# 0127-sd-card-micro.net
KiCad netlist of a schematic drawn in EAGLE
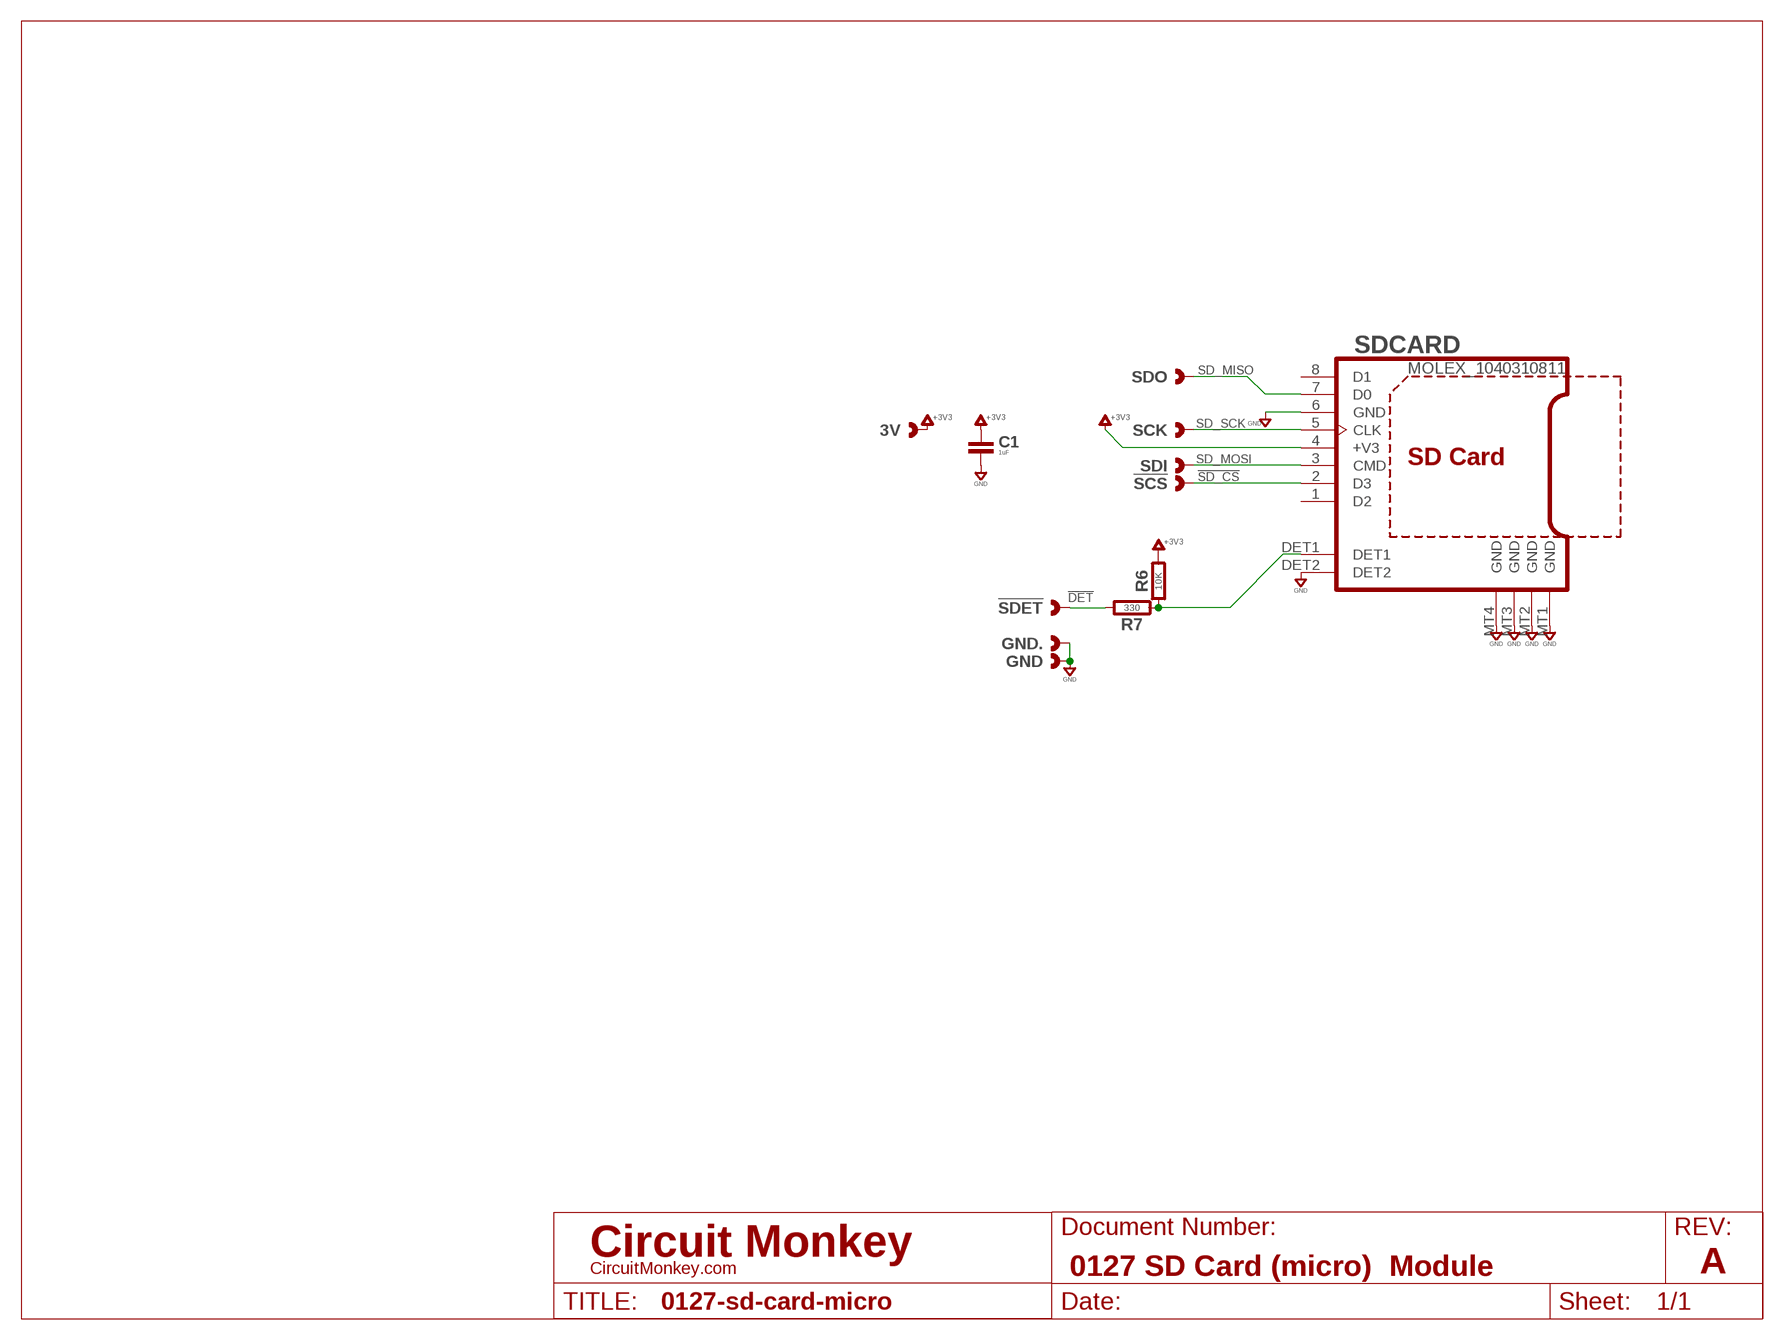
[diagram p0: schematic, sheet 1]

(export (version "E")
  (design (tool "Eeschema 10.0.6"))
  (components
    (comp (ref "!SCS")
      (value "CAST-01X12.00MM")
      (footprint "eagle-import:CAST01-2.00MM")
      (libsource (lib "eagle-import") (part "CAST-01X12.00MM"))
    )
    (comp (ref "!SDET")
      (value "CAST-01X12.00MM")
      (footprint "eagle-import:CAST01-2.00MM")
      (libsource (lib "eagle-import") (part "CAST-01X12.00MM"))
    )
    (comp (ref "3V")
      (value "CAST-01X12.00MM")
      (footprint "eagle-import:CAST01-2.00MM")
      (libsource (lib "eagle-import") (part "CAST-01X12.00MM"))
    )
    (comp (ref "C1")
      (value "1uF")
      (footprint "eagle-import:0603-CAP")
      (libsource (lib "eagle-import") (part "CAPACITOR0603"))
    )
    (comp (ref "GND")
      (value "CAST-01X12.00MM")
      (footprint "eagle-import:CAST01-2.00MM")
      (libsource (lib "eagle-import") (part "CAST-01X12.00MM"))
    )
    (comp (ref "GND.")
      (value "CAST-01X12.00MM")
      (footprint "eagle-import:CAST01-2.00MM")
      (libsource (lib "eagle-import") (part "CAST-01X12.00MM"))
    )
    (comp (ref "R6")
      (value "10K")
      (footprint "eagle-import:0603-RES")
      (libsource (lib "eagle-import") (part "RESISTOR0603"))
    )
    (comp (ref "R7")
      (value "330")
      (footprint "eagle-import:0603-RES")
      (libsource (lib "eagle-import") (part "RESISTOR0603"))
    )
    (comp (ref "SCK")
      (value "CAST-01X12.00MM")
      (footprint "eagle-import:CAST01-2.00MM")
      (libsource (lib "eagle-import") (part "CAST-01X12.00MM"))
    )
    (comp (ref "SDCARD")
      (value "MOLEX_1040310811")
      (footprint "eagle-import:MOLEX_1040310811_USD")
      (fields (field (name "MFR") "Molex") (field (name "MPN") "1040310811"))
      (libsource (lib "eagle-import") (part "MICRO-SD-CARDMOLEX-1040310811"))
    )
    (comp (ref "SDI")
      (value "CAST-01X12.00MM")
      (footprint "eagle-import:CAST01-2.00MM")
      (libsource (lib "eagle-import") (part "CAST-01X12.00MM"))
    )
    (comp (ref "SDO")
      (value "CAST-01X12.00MM")
      (footprint "eagle-import:CAST01-2.00MM")
      (libsource (lib "eagle-import") (part "CAST-01X12.00MM"))
    )
  )
  (nets
    (net (code "1") (name "+3V3") (class "Default")
      (node (ref "3V") (pin "1") (pinfunction "1_1") (pintype "bidirectional"))
      (node (ref "3V") (pin "P$1") (pinfunction "1_P$1") (pintype "bidirectional"))
      (node (ref "3V") (pin "P$2") (pinfunction "1_P$2") (pintype "bidirectional"))
      (node (ref "C1") (pin "1") (pinfunction "1_1") (pintype "passive"))
      (node (ref "R6") (pin "2") (pinfunction "2_2") (pintype "passive"))
      (node (ref "SDCARD") (pin "4") (pinfunction "+V3_4") (pintype "power_in"))
    )
    (net (code "2") (name "/SD_MISO") (class "Default")
      (node (ref "SDCARD") (pin "7") (pinfunction "D0_7") (pintype "bidirectional"))
      (node (ref "SDO") (pin "1") (pinfunction "1_1") (pintype "bidirectional"))
      (node (ref "SDO") (pin "P$1") (pinfunction "1_P$1") (pintype "bidirectional"))
      (node (ref "SDO") (pin "P$2") (pinfunction "1_P$2") (pintype "bidirectional"))
    )
    (net (code "3") (name "/SD_MOSI") (class "Default")
      (node (ref "SDCARD") (pin "3") (pinfunction "CMD_3") (pintype "bidirectional"))
      (node (ref "SDI") (pin "1") (pinfunction "1_1") (pintype "bidirectional"))
      (node (ref "SDI") (pin "P$1") (pinfunction "1_P$1") (pintype "bidirectional"))
      (node (ref "SDI") (pin "P$2") (pinfunction "1_P$2") (pintype "bidirectional"))
    )
    (net (code "4") (name "/SD_SCK") (class "Default")
      (node (ref "SCK") (pin "1") (pinfunction "1_1") (pintype "bidirectional"))
      (node (ref "SCK") (pin "P$1") (pinfunction "1_P$1") (pintype "bidirectional"))
      (node (ref "SCK") (pin "P$2") (pinfunction "1_P$2") (pintype "bidirectional"))
      (node (ref "SDCARD") (pin "5") (pinfunction "CLK_5") (pintype "input"))
    )
    (net (code "5") (name "/~{DET}") (class "Default")
      (node (ref "!SDET") (pin "1") (pinfunction "1_1") (pintype "bidirectional"))
      (node (ref "!SDET") (pin "P$1") (pinfunction "1_P$1") (pintype "bidirectional"))
      (node (ref "!SDET") (pin "P$2") (pinfunction "1_P$2") (pintype "bidirectional"))
      (node (ref "R7") (pin "2") (pinfunction "2_2") (pintype "passive"))
    )
    (net (code "6") (name "/~{SD_CS}") (class "Default")
      (node (ref "!SCS") (pin "1") (pinfunction "1_1") (pintype "bidirectional"))
      (node (ref "!SCS") (pin "P$1") (pinfunction "1_P$1") (pintype "bidirectional"))
      (node (ref "!SCS") (pin "P$2") (pinfunction "1_P$2") (pintype "bidirectional"))
      (node (ref "SDCARD") (pin "2") (pinfunction "D3_2") (pintype "bidirectional"))
    )
    (net (code "7") (name "GND") (class "Default")
      (node (ref "C1") (pin "2") (pinfunction "2_2") (pintype "passive"))
      (node (ref "GND") (pin "1") (pinfunction "1_1") (pintype "bidirectional"))
      (node (ref "GND") (pin "P$1") (pinfunction "1_P$1") (pintype "bidirectional"))
      (node (ref "GND") (pin "P$2") (pinfunction "1_P$2") (pintype "bidirectional"))
      (node (ref "GND.") (pin "1") (pinfunction "1_1") (pintype "bidirectional"))
      (node (ref "GND.") (pin "P$1") (pinfunction "1_P$1") (pintype "bidirectional"))
      (node (ref "GND.") (pin "P$2") (pinfunction "1_P$2") (pintype "bidirectional"))
      (node (ref "SDCARD") (pin "6") (pinfunction "GND_6") (pintype "power_in"))
      (node (ref "SDCARD") (pin "DET2") (pinfunction "DET2_DET2") (pintype "passive"))
      (node (ref "SDCARD") (pin "MT1") (pinfunction "GND_MT1") (pintype "power_in"))
      (node (ref "SDCARD") (pin "MT2") (pinfunction "GND_MT2") (pintype "power_in"))
      (node (ref "SDCARD") (pin "MT3") (pinfunction "GND_MT3") (pintype "power_in"))
      (node (ref "SDCARD") (pin "MT4") (pinfunction "GND_MT4") (pintype "power_in"))
    )
    (net (code "8") (name "Net-(R6-Pad1)") (class "Default")
      (node (ref "R6") (pin "1") (pinfunction "1_1") (pintype "passive"))
      (node (ref "R7") (pin "1") (pinfunction "1_1") (pintype "passive"))
      (node (ref "SDCARD") (pin "DET1") (pinfunction "DET1_DET1") (pintype "passive"))
    )
    (net (code "9") (name "unconnected-(SDCARD-D1-Pad8)") (class "Default")
      (node (ref "SDCARD") (pin "8") (pinfunction "D1_8") (pintype "bidirectional"))
    )
    (net (code "10") (name "unconnected-(SDCARD-D2-Pad1)") (class "Default")
      (node (ref "SDCARD") (pin "1") (pinfunction "D2_1") (pintype "bidirectional"))
    )
  )
)
